# shield_confortimetro_1_1.net
KiCad netlist of a schematic drawn in EAGLE
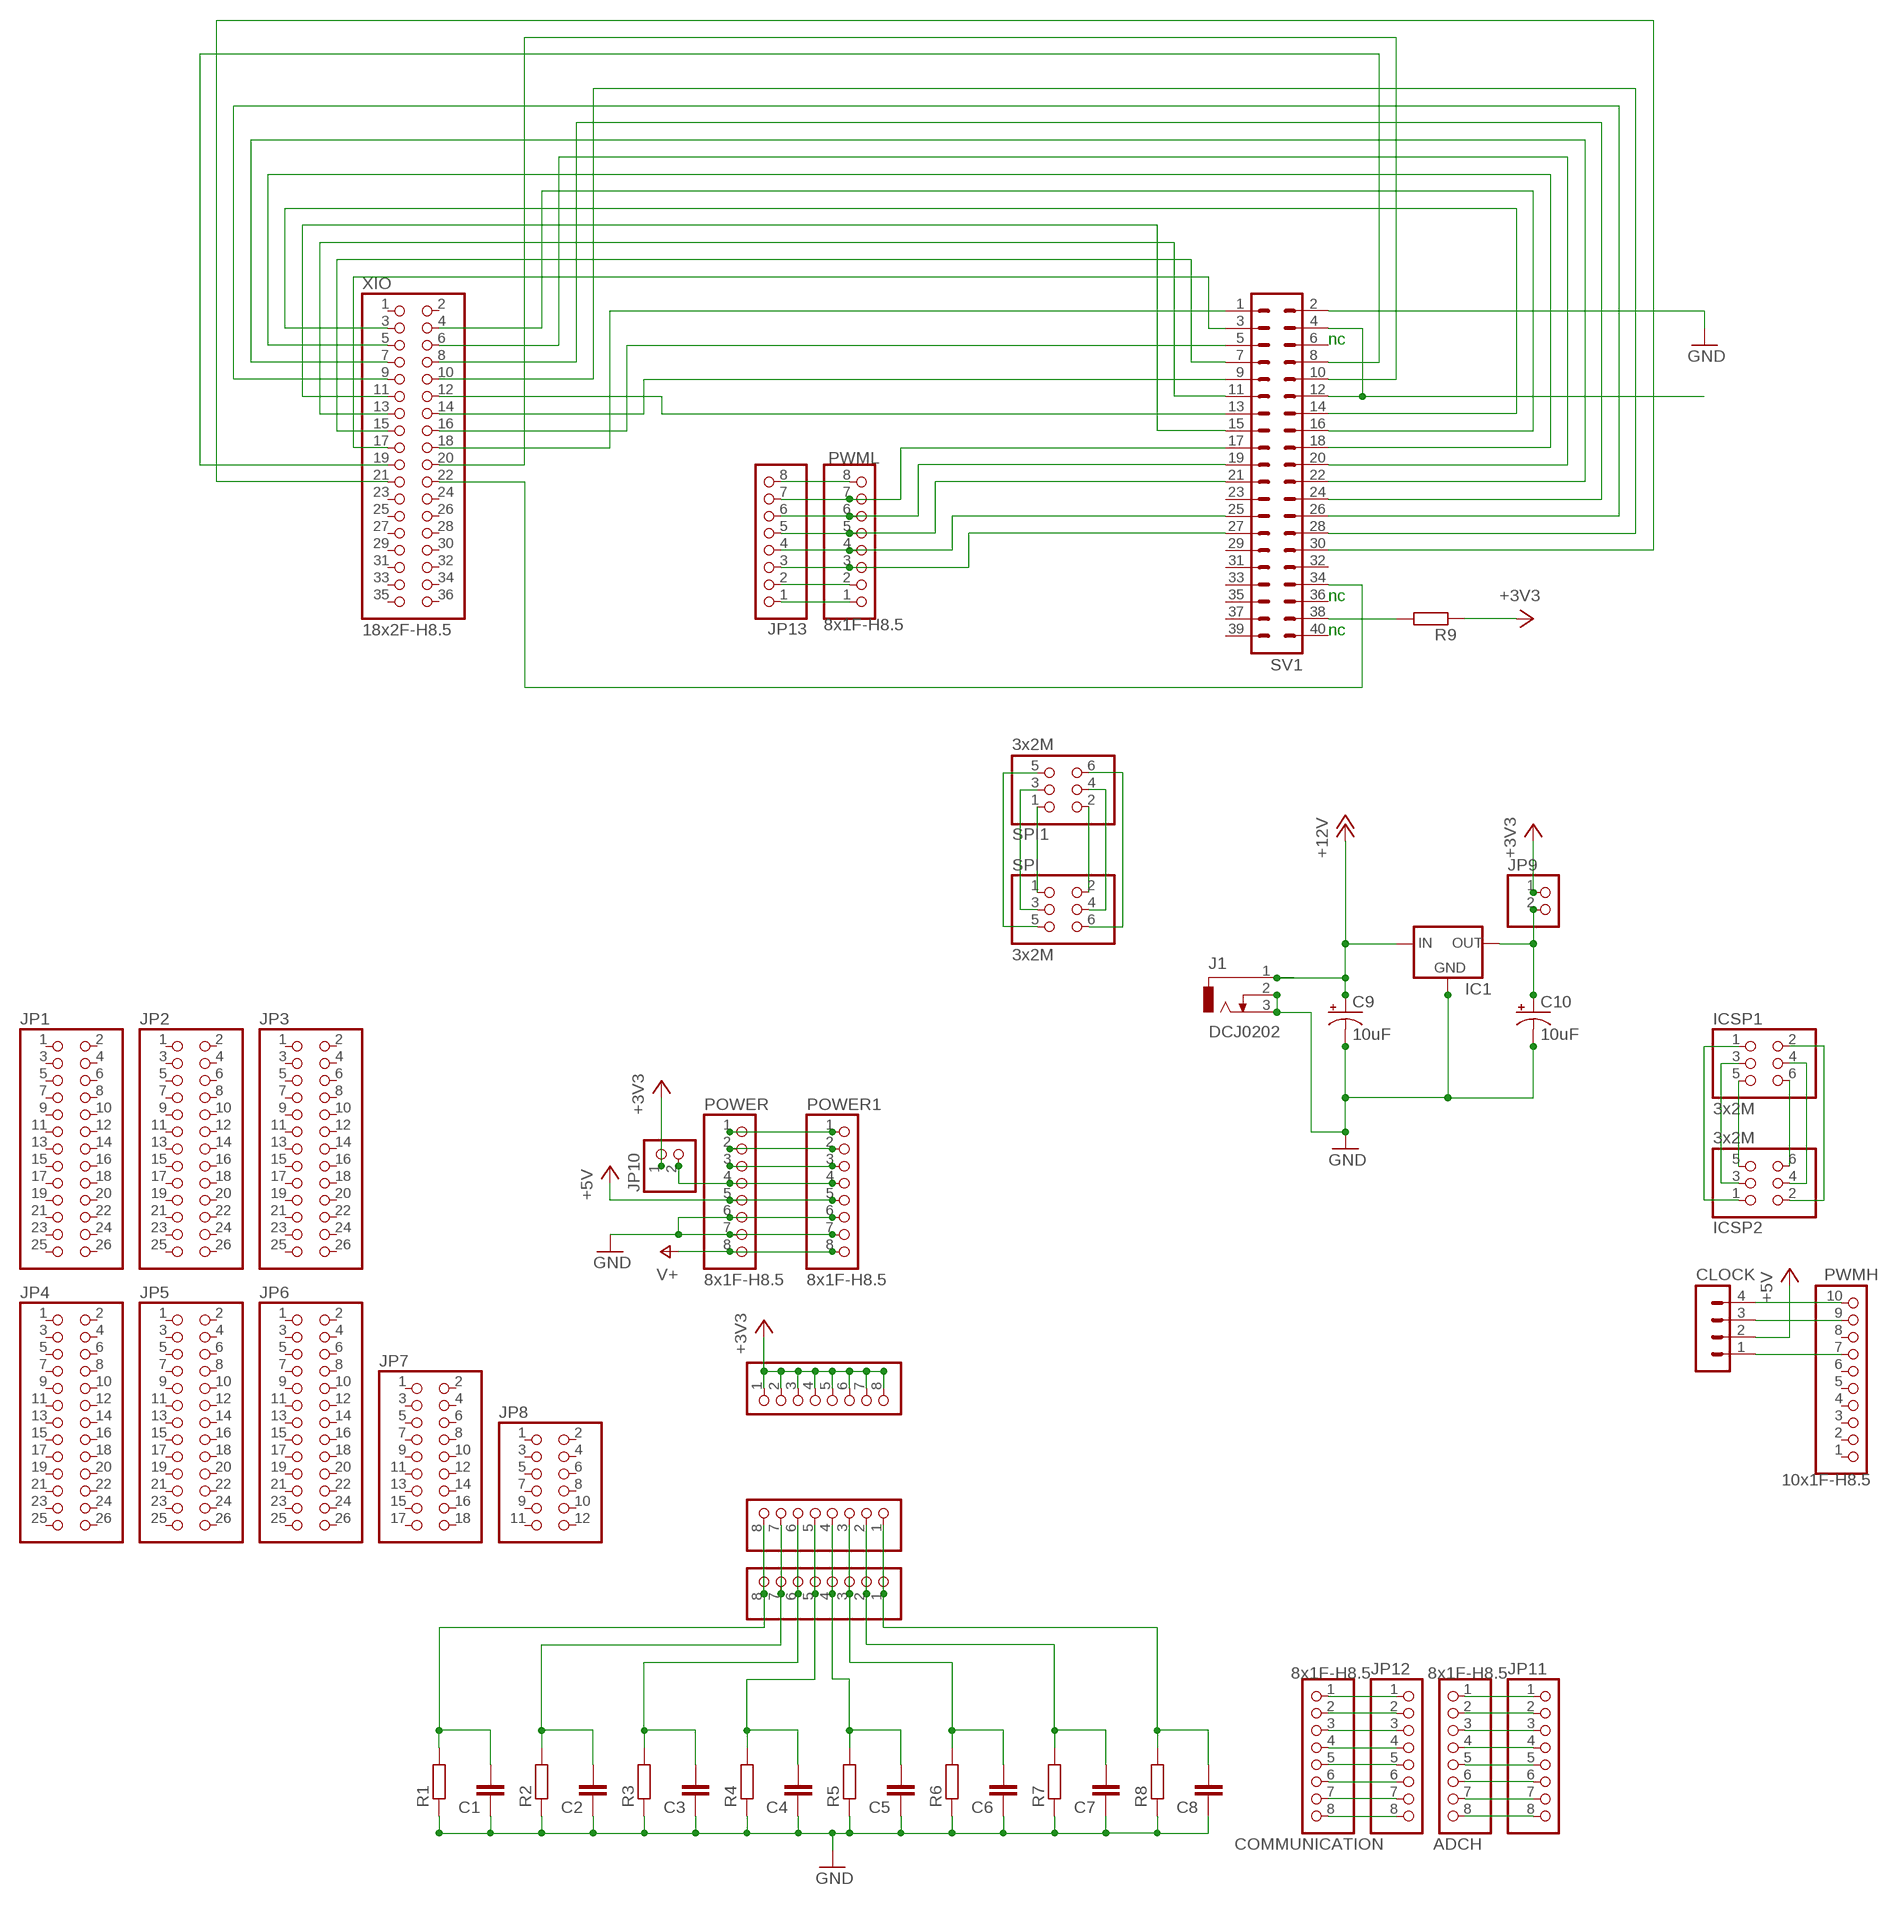
[diagram p0: schematic, sheet 1]

(export (version "E")
  (design (tool "Eeschema 10.0.6"))
  (components
    (comp (ref "ADCH")
      (value "8x1F-H8.5")
      (footprint "eagle-import:1X08")
      (libsource (lib "eagle-import") (part "PINHD-1X8"))
    )
    (comp (ref "ADCL")
      (value "8x1F-H8.5")
      (footprint "eagle-import:1X08")
      (libsource (lib "eagle-import") (part "PINHD-1X8"))
    )
    (comp (ref "C1")
      (value "C5/2.5")
      (footprint "eagle-import:C5B2.5")
      (libsource (lib "eagle-import") (part "C5/2.5"))
    )
    (comp (ref "C2")
      (value "C5/2.5")
      (footprint "eagle-import:C5B2.5")
      (libsource (lib "eagle-import") (part "C5/2.5"))
    )
    (comp (ref "C3")
      (value "C5/2.5")
      (footprint "eagle-import:C5B2.5")
      (libsource (lib "eagle-import") (part "C5/2.5"))
    )
    (comp (ref "C4")
      (value "C5/2.5")
      (footprint "eagle-import:C5B2.5")
      (libsource (lib "eagle-import") (part "C5/2.5"))
    )
    (comp (ref "C5")
      (value "C5/2.5")
      (footprint "eagle-import:C5B2.5")
      (libsource (lib "eagle-import") (part "C5/2.5"))
    )
    (comp (ref "C6")
      (value "C5/2.5")
      (footprint "eagle-import:C5B2.5")
      (libsource (lib "eagle-import") (part "C5/2.5"))
    )
    (comp (ref "C7")
      (value "C5/2.5")
      (footprint "eagle-import:C5B2.5")
      (libsource (lib "eagle-import") (part "C5/2.5"))
    )
    (comp (ref "C8")
      (value "C5/2.5")
      (footprint "eagle-import:C5B2.5")
      (libsource (lib "eagle-import") (part "C5/2.5"))
    )
    (comp (ref "C9")
      (value "10uF")
      (footprint "eagle-import:E2-5")
      (libsource (lib "eagle-import") (part "CPOL-USE2-5"))
    )
    (comp (ref "C10")
      (value "10uF")
      (footprint "eagle-import:E2-5")
      (libsource (lib "eagle-import") (part "CPOL-USE2-5"))
    )
    (comp (ref "CLOCK")
      (value "MA04-1")
      (footprint "eagle-import:MA04-1")
      (libsource (lib "eagle-import") (part "MA04-1"))
    )
    (comp (ref "COMMUNICATION")
      (value "8x1F-H8.5")
      (footprint "eagle-import:1X08")
      (libsource (lib "eagle-import") (part "PINHD-1X8"))
    )
    (comp (ref "IC1")
      (value "78XXL")
      (footprint "eagle-import:78XXL")
      (libsource (lib "eagle-import") (part "78XXL"))
    )
    (comp (ref "ICSP1")
      (value "3x2M")
      (footprint "eagle-import:2X03")
      (libsource (lib "eagle-import") (part "PINHD-2X3"))
    )
    (comp (ref "ICSP2")
      (value "3x2M")
      (footprint "eagle-import:2X03")
      (libsource (lib "eagle-import") (part "PINHD-2X3"))
    )
    (comp (ref "J1")
      (value "DCJ0202")
      (footprint "eagle-import:DCJ0202")
      (libsource (lib "eagle-import") (part "DCJ0202"))
    )
    (comp (ref "JP1")
      (value "PINHD-2X13")
      (footprint "eagle-import:2X13")
      (libsource (lib "eagle-import") (part "PINHD-2X13"))
    )
    (comp (ref "JP2")
      (value "PINHD-2X13")
      (footprint "eagle-import:2X13")
      (libsource (lib "eagle-import") (part "PINHD-2X13"))
    )
    (comp (ref "JP3")
      (value "PINHD-2X13")
      (footprint "eagle-import:2X13")
      (libsource (lib "eagle-import") (part "PINHD-2X13"))
    )
    (comp (ref "JP4")
      (value "PINHD-2X13")
      (footprint "eagle-import:2X13")
      (libsource (lib "eagle-import") (part "PINHD-2X13"))
    )
    (comp (ref "JP5")
      (value "PINHD-2X13")
      (footprint "eagle-import:2X13")
      (libsource (lib "eagle-import") (part "PINHD-2X13"))
    )
    (comp (ref "JP6")
      (value "PINHD-2X13")
      (footprint "eagle-import:2X13")
      (libsource (lib "eagle-import") (part "PINHD-2X13"))
    )
    (comp (ref "JP7")
      (value "PINHD-2X9")
      (footprint "eagle-import:2X09")
      (libsource (lib "eagle-import") (part "PINHD-2X9"))
    )
    (comp (ref "JP8")
      (value "PINHD-2X6")
      (footprint "eagle-import:2X06")
      (libsource (lib "eagle-import") (part "PINHD-2X6"))
    )
    (comp (ref "JP9")
      (value "PINHD-1X2")
      (footprint "eagle-import:1X02")
      (libsource (lib "eagle-import") (part "PINHD-1X2"))
    )
    (comp (ref "JP10")
      (value "PINHD-1X2")
      (footprint "eagle-import:1X02")
      (libsource (lib "eagle-import") (part "PINHD-1X2"))
    )
    (comp (ref "JP11")
      (value "PINHD-1X8")
      (footprint "eagle-import:1X08")
      (libsource (lib "eagle-import") (part "pinhead_PINHD-1X8"))
    )
    (comp (ref "JP12")
      (value "PINHD-1X8")
      (footprint "eagle-import:1X08")
      (libsource (lib "eagle-import") (part "pinhead_PINHD-1X8"))
    )
    (comp (ref "JP13")
      (value "PINHD-1X8")
      (footprint "eagle-import:1X08")
      (libsource (lib "eagle-import") (part "pinhead_PINHD-1X8"))
    )
    (comp (ref "POWER")
      (value "8x1F-H8.5")
      (footprint "eagle-import:1X08")
      (libsource (lib "eagle-import") (part "PINHD-1X8"))
    )
    (comp (ref "POWER1")
      (value "8x1F-H8.5")
      (footprint "eagle-import:1X08")
      (libsource (lib "eagle-import") (part "PINHD-1X8"))
    )
    (comp (ref "PWMH")
      (value "10x1F-H8.5")
      (footprint "eagle-import:1X10")
      (libsource (lib "eagle-import") (part "PINHD-1X10"))
    )
    (comp (ref "PWML")
      (value "8x1F-H8.5")
      (footprint "eagle-import:1X08")
      (libsource (lib "eagle-import") (part "PINHD-1X8"))
    )
    (comp (ref "PWML1")
      (value "8x1F-H8.5")
      (footprint "eagle-import:1X08")
      (libsource (lib "eagle-import") (part "PINHD-1X8"))
    )
    (comp (ref "PWML2")
      (value "8x1F-H8.5")
      (footprint "eagle-import:1X08")
      (libsource (lib "eagle-import") (part "PINHD-1X8"))
    )
    (comp (ref "R1")
      (value "R-EU_0204/7")
      (footprint "eagle-import:0204_7")
      (libsource (lib "eagle-import") (part "R-EU_0204/7"))
    )
    (comp (ref "R2")
      (value "R-EU_0204/7")
      (footprint "eagle-import:0204_7")
      (libsource (lib "eagle-import") (part "R-EU_0204/7"))
    )
    (comp (ref "R3")
      (value "R-EU_0204/7")
      (footprint "eagle-import:0204_7")
      (libsource (lib "eagle-import") (part "R-EU_0204/7"))
    )
    (comp (ref "R4")
      (value "R-EU_0204/7")
      (footprint "eagle-import:0204_7")
      (libsource (lib "eagle-import") (part "R-EU_0204/7"))
    )
    (comp (ref "R5")
      (value "R-EU_0204/7")
      (footprint "eagle-import:0204_7")
      (libsource (lib "eagle-import") (part "R-EU_0204/7"))
    )
    (comp (ref "R6")
      (value "R-EU_0204/7")
      (footprint "eagle-import:0204_7")
      (libsource (lib "eagle-import") (part "R-EU_0204/7"))
    )
    (comp (ref "R7")
      (value "R-EU_0204/7")
      (footprint "eagle-import:0204_7")
      (libsource (lib "eagle-import") (part "R-EU_0204/7"))
    )
    (comp (ref "R8")
      (value "R-EU_0204/7")
      (footprint "eagle-import:0204_7")
      (libsource (lib "eagle-import") (part "R-EU_0204/7"))
    )
    (comp (ref "R9")
      (value "R-EU_0204/7")
      (footprint "eagle-import:0204_7")
      (libsource (lib "eagle-import") (part "R-EU_0204/7"))
    )
    (comp (ref "SPI")
      (value "3x2M")
      (footprint "eagle-import:2X03")
      (libsource (lib "eagle-import") (part "PINHD-2X3"))
    )
    (comp (ref "SPI1")
      (value "3x2M")
      (footprint "eagle-import:2X03")
      (libsource (lib "eagle-import") (part "PINHD-2X3"))
    )
    (comp (ref "SV1")
      (value "ML40")
      (footprint "eagle-import:ML40")
      (libsource (lib "eagle-import") (part "ML40"))
    )
    (comp (ref "XIO")
      (value "18x2F-H8.5")
      (footprint "eagle-import:2X18")
      (libsource (lib "eagle-import") (part "PINHD-2X18"))
    )
  )
  (nets
    (net (code "1") (name "+3V3") (class "Default")
      (node (ref "JP10") (pin "1") (pinfunction "1_1") (pintype "passive"))
      (node (ref "JP9") (pin "1") (pinfunction "1_1") (pintype "passive"))
      (node (ref "PWML2") (pin "1") (pinfunction "1_1") (pintype "passive"))
      (node (ref "PWML2") (pin "2") (pinfunction "2_2") (pintype "passive"))
      (node (ref "PWML2") (pin "3") (pinfunction "3_3") (pintype "passive"))
      (node (ref "PWML2") (pin "4") (pinfunction "4_4") (pintype "passive"))
      (node (ref "PWML2") (pin "5") (pinfunction "5_5") (pintype "passive"))
      (node (ref "PWML2") (pin "6") (pinfunction "6_6") (pintype "passive"))
      (node (ref "PWML2") (pin "7") (pinfunction "7_7") (pintype "passive"))
      (node (ref "PWML2") (pin "8") (pinfunction "8_8") (pintype "passive"))
      (node (ref "R9") (pin "1") (pinfunction "1_1") (pintype "passive"))
    )
    (net (code "2") (name "+5V") (class "Default")
      (node (ref "CLOCK") (pin "2") (pinfunction "2_2") (pintype "passive"))
      (node (ref "POWER") (pin "5") (pinfunction "5_5") (pintype "passive"))
      (node (ref "POWER1") (pin "5") (pinfunction "5_5") (pintype "passive"))
    )
    (net (code "3") (name "+12V") (class "Default")
      (node (ref "C9") (pin "+") (pinfunction "+_+") (pintype "passive"))
      (node (ref "IC1") (pin "IN") (pinfunction "IN_IN") (pintype "input"))
      (node (ref "J1") (pin "1") (pinfunction "1_1") (pintype "passive"))
    )
    (net (code "4") (name "GND") (class "Default")
      (node (ref "C1") (pin "1") (pinfunction "1_1") (pintype "passive"))
      (node (ref "C10") (pin "-") (pinfunction "-_-") (pintype "passive"))
      (node (ref "C2") (pin "1") (pinfunction "1_1") (pintype "passive"))
      (node (ref "C3") (pin "1") (pinfunction "1_1") (pintype "passive"))
      (node (ref "C4") (pin "1") (pinfunction "1_1") (pintype "passive"))
      (node (ref "C5") (pin "1") (pinfunction "1_1") (pintype "passive"))
      (node (ref "C6") (pin "1") (pinfunction "1_1") (pintype "passive"))
      (node (ref "C7") (pin "1") (pinfunction "1_1") (pintype "passive"))
      (node (ref "C8") (pin "1") (pinfunction "1_1") (pintype "passive"))
      (node (ref "C9") (pin "-") (pinfunction "-_-") (pintype "passive"))
      (node (ref "IC1") (pin "GND") (pinfunction "GND_GND") (pintype "input"))
      (node (ref "J1") (pin "2") (pinfunction "2_2") (pintype "passive"))
      (node (ref "J1") (pin "3") (pinfunction "3_3") (pintype "passive"))
      (node (ref "POWER") (pin "6") (pinfunction "6_6") (pintype "passive"))
      (node (ref "POWER") (pin "7") (pinfunction "7_7") (pintype "passive"))
      (node (ref "POWER1") (pin "6") (pinfunction "6_6") (pintype "passive"))
      (node (ref "POWER1") (pin "7") (pinfunction "7_7") (pintype "passive"))
      (node (ref "R1") (pin "1") (pinfunction "1_1") (pintype "passive"))
      (node (ref "R2") (pin "1") (pinfunction "1_1") (pintype "passive"))
      (node (ref "R3") (pin "1") (pinfunction "1_1") (pintype "passive"))
      (node (ref "R4") (pin "1") (pinfunction "1_1") (pintype "passive"))
      (node (ref "R5") (pin "1") (pinfunction "1_1") (pintype "passive"))
      (node (ref "R6") (pin "1") (pinfunction "1_1") (pintype "passive"))
      (node (ref "R7") (pin "1") (pinfunction "1_1") (pintype "passive"))
      (node (ref "R8") (pin "1") (pinfunction "1_1") (pintype "passive"))
      (node (ref "SV1") (pin "2") (pinfunction "2_2") (pintype "passive"))
    )
    (net (code "5") (name "Net-(ADCH-Pad1)") (class "Default")
      (node (ref "ADCH") (pin "1") (pinfunction "1_1") (pintype "passive"))
      (node (ref "JP11") (pin "1") (pinfunction "1_1") (pintype "passive"))
    )
    (net (code "6") (name "Net-(ADCH-Pad2)") (class "Default")
      (node (ref "ADCH") (pin "2") (pinfunction "2_2") (pintype "passive"))
      (node (ref "JP11") (pin "2") (pinfunction "2_2") (pintype "passive"))
    )
    (net (code "7") (name "Net-(ADCH-Pad3)") (class "Default")
      (node (ref "ADCH") (pin "3") (pinfunction "3_3") (pintype "passive"))
      (node (ref "JP11") (pin "3") (pinfunction "3_3") (pintype "passive"))
    )
    (net (code "8") (name "Net-(ADCH-Pad4)") (class "Default")
      (node (ref "ADCH") (pin "4") (pinfunction "4_4") (pintype "passive"))
      (node (ref "JP11") (pin "4") (pinfunction "4_4") (pintype "passive"))
    )
    (net (code "9") (name "Net-(ADCH-Pad5)") (class "Default")
      (node (ref "ADCH") (pin "5") (pinfunction "5_5") (pintype "passive"))
      (node (ref "JP11") (pin "5") (pinfunction "5_5") (pintype "passive"))
    )
    (net (code "10") (name "Net-(ADCH-Pad6)") (class "Default")
      (node (ref "ADCH") (pin "6") (pinfunction "6_6") (pintype "passive"))
      (node (ref "JP11") (pin "6") (pinfunction "6_6") (pintype "passive"))
    )
    (net (code "11") (name "Net-(ADCH-Pad7)") (class "Default")
      (node (ref "ADCH") (pin "7") (pinfunction "7_7") (pintype "passive"))
      (node (ref "JP11") (pin "7") (pinfunction "7_7") (pintype "passive"))
    )
    (net (code "12") (name "Net-(ADCH-Pad8)") (class "Default")
      (node (ref "ADCH") (pin "8") (pinfunction "8_8") (pintype "passive"))
      (node (ref "JP11") (pin "8") (pinfunction "8_8") (pintype "passive"))
    )
    (net (code "13") (name "Net-(ADCL-Pad1)") (class "Default")
      (node (ref "ADCL") (pin "1") (pinfunction "1_1") (pintype "passive"))
      (node (ref "C8") (pin "2") (pinfunction "2_2") (pintype "passive"))
      (node (ref "PWML1") (pin "1") (pinfunction "1_1") (pintype "passive"))
      (node (ref "R8") (pin "2") (pinfunction "2_2") (pintype "passive"))
    )
    (net (code "14") (name "Net-(ADCL-Pad2)") (class "Default")
      (node (ref "ADCL") (pin "2") (pinfunction "2_2") (pintype "passive"))
      (node (ref "C7") (pin "2") (pinfunction "2_2") (pintype "passive"))
      (node (ref "PWML1") (pin "2") (pinfunction "2_2") (pintype "passive"))
      (node (ref "R7") (pin "2") (pinfunction "2_2") (pintype "passive"))
    )
    (net (code "15") (name "Net-(ADCL-Pad3)") (class "Default")
      (node (ref "ADCL") (pin "3") (pinfunction "3_3") (pintype "passive"))
      (node (ref "C6") (pin "2") (pinfunction "2_2") (pintype "passive"))
      (node (ref "PWML1") (pin "3") (pinfunction "3_3") (pintype "passive"))
      (node (ref "R6") (pin "2") (pinfunction "2_2") (pintype "passive"))
    )
    (net (code "16") (name "Net-(ADCL-Pad4)") (class "Default")
      (node (ref "ADCL") (pin "4") (pinfunction "4_4") (pintype "passive"))
      (node (ref "C5") (pin "2") (pinfunction "2_2") (pintype "passive"))
      (node (ref "PWML1") (pin "4") (pinfunction "4_4") (pintype "passive"))
      (node (ref "R5") (pin "2") (pinfunction "2_2") (pintype "passive"))
    )
    (net (code "17") (name "Net-(ADCL-Pad5)") (class "Default")
      (node (ref "ADCL") (pin "5") (pinfunction "5_5") (pintype "passive"))
      (node (ref "C4") (pin "2") (pinfunction "2_2") (pintype "passive"))
      (node (ref "PWML1") (pin "5") (pinfunction "5_5") (pintype "passive"))
      (node (ref "R4") (pin "2") (pinfunction "2_2") (pintype "passive"))
    )
    (net (code "18") (name "Net-(ADCL-Pad6)") (class "Default")
      (node (ref "ADCL") (pin "6") (pinfunction "6_6") (pintype "passive"))
      (node (ref "C3") (pin "2") (pinfunction "2_2") (pintype "passive"))
      (node (ref "PWML1") (pin "6") (pinfunction "6_6") (pintype "passive"))
      (node (ref "R3") (pin "2") (pinfunction "2_2") (pintype "passive"))
    )
    (net (code "19") (name "Net-(ADCL-Pad7)") (class "Default")
      (node (ref "ADCL") (pin "7") (pinfunction "7_7") (pintype "passive"))
      (node (ref "C2") (pin "2") (pinfunction "2_2") (pintype "passive"))
      (node (ref "PWML1") (pin "7") (pinfunction "7_7") (pintype "passive"))
      (node (ref "R2") (pin "2") (pinfunction "2_2") (pintype "passive"))
    )
    (net (code "20") (name "Net-(ADCL-Pad8)") (class "Default")
      (node (ref "ADCL") (pin "8") (pinfunction "8_8") (pintype "passive"))
      (node (ref "C1") (pin "2") (pinfunction "2_2") (pintype "passive"))
      (node (ref "PWML1") (pin "8") (pinfunction "8_8") (pintype "passive"))
      (node (ref "R1") (pin "2") (pinfunction "2_2") (pintype "passive"))
    )
    (net (code "21") (name "Net-(C10-Pad+)") (class "Default")
      (node (ref "C10") (pin "+") (pinfunction "+_+") (pintype "passive"))
      (node (ref "IC1") (pin "OUT") (pinfunction "OUT_OUT") (pintype "passive"))
      (node (ref "JP9") (pin "2") (pinfunction "2_2") (pintype "passive"))
    )
    (net (code "22") (name "Net-(CLOCK-Pad1)") (class "Default")
      (node (ref "CLOCK") (pin "1") (pinfunction "1_1") (pintype "passive"))
      (node (ref "PWMH") (pin "7") (pinfunction "7_7") (pintype "passive"))
    )
    (net (code "23") (name "Net-(CLOCK-Pad3)") (class "Default")
      (node (ref "CLOCK") (pin "3") (pinfunction "3_3") (pintype "passive"))
      (node (ref "PWMH") (pin "9") (pinfunction "9_9") (pintype "passive"))
    )
    (net (code "24") (name "Net-(CLOCK-Pad4)") (class "Default")
      (node (ref "CLOCK") (pin "4") (pinfunction "4_4") (pintype "passive"))
      (node (ref "PWMH") (pin "10") (pinfunction "10_10") (pintype "passive"))
    )
    (net (code "25") (name "Net-(COMMUNICATION-Pad1)") (class "Default")
      (node (ref "COMMUNICATION") (pin "1") (pinfunction "1_1") (pintype "passive"))
      (node (ref "JP12") (pin "1") (pinfunction "1_1") (pintype "passive"))
    )
    (net (code "26") (name "Net-(COMMUNICATION-Pad2)") (class "Default")
      (node (ref "COMMUNICATION") (pin "2") (pinfunction "2_2") (pintype "passive"))
      (node (ref "JP12") (pin "2") (pinfunction "2_2") (pintype "passive"))
    )
    (net (code "27") (name "Net-(COMMUNICATION-Pad3)") (class "Default")
      (node (ref "COMMUNICATION") (pin "3") (pinfunction "3_3") (pintype "passive"))
      (node (ref "JP12") (pin "3") (pinfunction "3_3") (pintype "passive"))
    )
    (net (code "28") (name "Net-(COMMUNICATION-Pad4)") (class "Default")
      (node (ref "COMMUNICATION") (pin "4") (pinfunction "4_4") (pintype "passive"))
      (node (ref "JP12") (pin "4") (pinfunction "4_4") (pintype "passive"))
    )
    (net (code "29") (name "Net-(COMMUNICATION-Pad5)") (class "Default")
      (node (ref "COMMUNICATION") (pin "5") (pinfunction "5_5") (pintype "passive"))
      (node (ref "JP12") (pin "5") (pinfunction "5_5") (pintype "passive"))
    )
    (net (code "30") (name "Net-(COMMUNICATION-Pad6)") (class "Default")
      (node (ref "COMMUNICATION") (pin "6") (pinfunction "6_6") (pintype "passive"))
      (node (ref "JP12") (pin "6") (pinfunction "6_6") (pintype "passive"))
    )
    (net (code "31") (name "Net-(COMMUNICATION-Pad7)") (class "Default")
      (node (ref "COMMUNICATION") (pin "7") (pinfunction "7_7") (pintype "passive"))
      (node (ref "JP12") (pin "7") (pinfunction "7_7") (pintype "passive"))
    )
    (net (code "32") (name "Net-(COMMUNICATION-Pad8)") (class "Default")
      (node (ref "COMMUNICATION") (pin "8") (pinfunction "8_8") (pintype "passive"))
      (node (ref "JP12") (pin "8") (pinfunction "8_8") (pintype "passive"))
    )
    (net (code "33") (name "Net-(ICSP1-Pad1)") (class "Default")
      (node (ref "ICSP1") (pin "1") (pinfunction "1_1") (pintype "passive"))
      (node (ref "ICSP2") (pin "1") (pinfunction "1_1") (pintype "passive"))
    )
    (net (code "34") (name "Net-(ICSP1-Pad2)") (class "Default")
      (node (ref "ICSP1") (pin "2") (pinfunction "2_2") (pintype "passive"))
      (node (ref "ICSP2") (pin "2") (pinfunction "2_2") (pintype "passive"))
    )
    (net (code "35") (name "Net-(ICSP1-Pad3)") (class "Default")
      (node (ref "ICSP1") (pin "3") (pinfunction "3_3") (pintype "passive"))
      (node (ref "ICSP2") (pin "3") (pinfunction "3_3") (pintype "passive"))
    )
    (net (code "36") (name "Net-(ICSP1-Pad4)") (class "Default")
      (node (ref "ICSP1") (pin "4") (pinfunction "4_4") (pintype "passive"))
      (node (ref "ICSP2") (pin "4") (pinfunction "4_4") (pintype "passive"))
    )
    (net (code "37") (name "Net-(ICSP1-Pad5)") (class "Default")
      (node (ref "ICSP1") (pin "5") (pinfunction "5_5") (pintype "passive"))
      (node (ref "ICSP2") (pin "5") (pinfunction "5_5") (pintype "passive"))
    )
    (net (code "38") (name "Net-(ICSP1-Pad6)") (class "Default")
      (node (ref "ICSP1") (pin "6") (pinfunction "6_6") (pintype "passive"))
      (node (ref "ICSP2") (pin "6") (pinfunction "6_6") (pintype "passive"))
    )
    (net (code "39") (name "Net-(JP10-Pad2)") (class "Default")
      (node (ref "JP10") (pin "2") (pinfunction "2_2") (pintype "passive"))
      (node (ref "POWER") (pin "4") (pinfunction "4_4") (pintype "passive"))
      (node (ref "POWER1") (pin "4") (pinfunction "4_4") (pintype "passive"))
    )
    (net (code "40") (name "Net-(JP13-Pad1)") (class "Default")
      (node (ref "JP13") (pin "1") (pinfunction "1_1") (pintype "passive"))
      (node (ref "PWML") (pin "1") (pinfunction "1_1") (pintype "passive"))
    )
    (net (code "41") (name "Net-(JP13-Pad2)") (class "Default")
      (node (ref "JP13") (pin "2") (pinfunction "2_2") (pintype "passive"))
      (node (ref "PWML") (pin "2") (pinfunction "2_2") (pintype "passive"))
    )
    (net (code "42") (name "Net-(JP13-Pad3)") (class "Default")
      (node (ref "JP13") (pin "3") (pinfunction "3_3") (pintype "passive"))
      (node (ref "PWML") (pin "3") (pinfunction "3_3") (pintype "passive"))
      (node (ref "SV1") (pin "27") (pinfunction "27_27") (pintype "passive"))
    )
    (net (code "43") (name "Net-(JP13-Pad4)") (class "Default")
      (node (ref "JP13") (pin "4") (pinfunction "4_4") (pintype "passive"))
      (node (ref "PWML") (pin "4") (pinfunction "4_4") (pintype "passive"))
      (node (ref "SV1") (pin "25") (pinfunction "25_25") (pintype "passive"))
    )
    (net (code "44") (name "Net-(JP13-Pad5)") (class "Default")
      (node (ref "JP13") (pin "5") (pinfunction "5_5") (pintype "passive"))
      (node (ref "PWML") (pin "5") (pinfunction "5_5") (pintype "passive"))
      (node (ref "SV1") (pin "21") (pinfunction "21_21") (pintype "passive"))
    )
    (net (code "45") (name "Net-(JP13-Pad6)") (class "Default")
      (node (ref "JP13") (pin "6") (pinfunction "6_6") (pintype "passive"))
      (node (ref "PWML") (pin "6") (pinfunction "6_6") (pintype "passive"))
      (node (ref "SV1") (pin "19") (pinfunction "19_19") (pintype "passive"))
    )
    (net (code "46") (name "Net-(JP13-Pad7)") (class "Default")
      (node (ref "JP13") (pin "7") (pinfunction "7_7") (pintype "passive"))
      (node (ref "PWML") (pin "7") (pinfunction "7_7") (pintype "passive"))
      (node (ref "SV1") (pin "17") (pinfunction "17_17") (pintype "passive"))
    )
    (net (code "47") (name "Net-(JP13-Pad8)") (class "Default")
      (node (ref "JP13") (pin "8") (pinfunction "8_8") (pintype "passive"))
      (node (ref "PWML") (pin "8") (pinfunction "8_8") (pintype "passive"))
    )
    (net (code "48") (name "Net-(POWER-Pad1)") (class "Default")
      (node (ref "POWER") (pin "1") (pinfunction "1_1") (pintype "passive"))
      (node (ref "POWER1") (pin "1") (pinfunction "1_1") (pintype "passive"))
    )
    (net (code "49") (name "Net-(POWER-Pad2)") (class "Default")
      (node (ref "POWER") (pin "2") (pinfunction "2_2") (pintype "passive"))
      (node (ref "POWER1") (pin "2") (pinfunction "2_2") (pintype "passive"))
    )
    (net (code "50") (name "Net-(POWER-Pad3)") (class "Default")
      (node (ref "POWER") (pin "3") (pinfunction "3_3") (pintype "passive"))
      (node (ref "POWER1") (pin "3") (pinfunction "3_3") (pintype "passive"))
    )
    (net (code "51") (name "Net-(R9-Pad2)") (class "Default")
      (node (ref "R9") (pin "2") (pinfunction "2_2") (pintype "passive"))
      (node (ref "SV1") (pin "38") (pinfunction "38_38") (pintype "passive"))
    )
    (net (code "52") (name "Net-(SPI-Pad1)") (class "Default")
      (node (ref "SPI") (pin "1") (pinfunction "1_1") (pintype "passive"))
      (node (ref "SPI1") (pin "1") (pinfunction "1_1") (pintype "passive"))
    )
    (net (code "53") (name "Net-(SPI-Pad2)") (class "Default")
      (node (ref "SPI") (pin "2") (pinfunction "2_2") (pintype "passive"))
      (node (ref "SPI1") (pin "2") (pinfunction "2_2") (pintype "passive"))
    )
    (net (code "54") (name "Net-(SPI-Pad3)") (class "Default")
      (node (ref "SPI") (pin "3") (pinfunction "3_3") (pintype "passive"))
      (node (ref "SPI1") (pin "3") (pinfunction "3_3") (pintype "passive"))
    )
    (net (code "55") (name "Net-(SPI-Pad4)") (class "Default")
      (node (ref "SPI") (pin "4") (pinfunction "4_4") (pintype "passive"))
      (node (ref "SPI1") (pin "4") (pinfunction "4_4") (pintype "passive"))
    )
    (net (code "56") (name "Net-(SPI-Pad5)") (class "Default")
      (node (ref "SPI") (pin "5") (pinfunction "5_5") (pintype "passive"))
      (node (ref "SPI1") (pin "5") (pinfunction "5_5") (pintype "passive"))
    )
    (net (code "57") (name "Net-(SPI-Pad6)") (class "Default")
      (node (ref "SPI") (pin "6") (pinfunction "6_6") (pintype "passive"))
      (node (ref "SPI1") (pin "6") (pinfunction "6_6") (pintype "passive"))
    )
    (net (code "58") (name "Net-(SV1-Pad1)") (class "Default")
      (node (ref "SV1") (pin "1") (pinfunction "1_1") (pintype "passive"))
      (node (ref "XIO") (pin "18") (pinfunction "18_18") (pintype "passive"))
    )
    (net (code "59") (name "Net-(SV1-Pad3)") (class "Default")
      (node (ref "SV1") (pin "3") (pinfunction "3_3") (pintype "passive"))
      (node (ref "XIO") (pin "17") (pinfunction "17_17") (pintype "passive"))
    )
    (net (code "60") (name "Net-(SV1-Pad5)") (class "Default")
      (node (ref "SV1") (pin "5") (pinfunction "5_5") (pintype "passive"))
      (node (ref "XIO") (pin "16") (pinfunction "16_16") (pintype "passive"))
    )
    (net (code "61") (name "Net-(SV1-Pad7)") (class "Default")
      (node (ref "SV1") (pin "7") (pinfunction "7_7") (pintype "passive"))
      (node (ref "XIO") (pin "15") (pinfunction "15_15") (pintype "passive"))
    )
    (net (code "62") (name "Net-(SV1-Pad8)") (class "Default")
      (node (ref "SV1") (pin "8") (pinfunction "8_8") (pintype "passive"))
      (node (ref "XIO") (pin "19") (pinfunction "19_19") (pintype "passive"))
    )
    (net (code "63") (name "Net-(SV1-Pad9)") (class "Default")
      (node (ref "SV1") (pin "9") (pinfunction "9_9") (pintype "passive"))
      (node (ref "XIO") (pin "14") (pinfunction "14_14") (pintype "passive"))
    )
    (net (code "64") (name "Net-(SV1-Pad10)") (class "Default")
      (node (ref "SV1") (pin "10") (pinfunction "10_10") (pintype "passive"))
      (node (ref "XIO") (pin "20") (pinfunction "20_20") (pintype "passive"))
    )
    (net (code "65") (name "Net-(SV1-Pad11)") (class "Default")
      (node (ref "SV1") (pin "11") (pinfunction "11_11") (pintype "passive"))
      (node (ref "XIO") (pin "13") (pinfunction "13_13") (pintype "passive"))
    )
    (net (code "66") (name "Net-(SV1-Pad12)") (class "Default")
      (node (ref "SV1") (pin "12") (pinfunction "12_12") (pintype "passive"))
      (node (ref "SV1") (pin "4") (pinfunction "4_4") (pintype "passive"))
    )
    (net (code "67") (name "Net-(SV1-Pad13)") (class "Default")
      (node (ref "SV1") (pin "13") (pinfunction "13_13") (pintype "passive"))
      (node (ref "XIO") (pin "12") (pinfunction "12_12") (pintype "passive"))
    )
    (net (code "68") (name "Net-(SV1-Pad14)") (class "Default")
      (node (ref "SV1") (pin "14") (pinfunction "14_14") (pintype "passive"))
      (node (ref "XIO") (pin "3") (pinfunction "3_3") (pintype "passive"))
    )
    (net (code "69") (name "Net-(SV1-Pad15)") (class "Default")
      (node (ref "SV1") (pin "15") (pinfunction "15_15") (pintype "passive"))
      (node (ref "XIO") (pin "11") (pinfunction "11_11") (pintype "passive"))
    )
    (net (code "70") (name "Net-(SV1-Pad16)") (class "Default")
      (node (ref "SV1") (pin "16") (pinfunction "16_16") (pintype "passive"))
      (node (ref "XIO") (pin "4") (pinfunction "4_4") (pintype "passive"))
    )
    (net (code "71") (name "Net-(SV1-Pad18)") (class "Default")
      (node (ref "SV1") (pin "18") (pinfunction "18_18") (pintype "passive"))
      (node (ref "XIO") (pin "5") (pinfunction "5_5") (pintype "passive"))
    )
    (net (code "72") (name "Net-(SV1-Pad20)") (class "Default")
      (node (ref "SV1") (pin "20") (pinfunction "20_20") (pintype "passive"))
      (node (ref "XIO") (pin "6") (pinfunction "6_6") (pintype "passive"))
    )
    (net (code "73") (name "Net-(SV1-Pad22)") (class "Default")
      (node (ref "SV1") (pin "22") (pinfunction "22_22") (pintype "passive"))
      (node (ref "XIO") (pin "7") (pinfunction "7_7") (pintype "passive"))
    )
    (net (code "74") (name "Net-(SV1-Pad24)") (class "Default")
      (node (ref "SV1") (pin "24") (pinfunction "24_24") (pintype "passive"))
      (node (ref "XIO") (pin "8") (pinfunction "8_8") (pintype "passive"))
    )
    (net (code "75") (name "Net-(SV1-Pad26)") (class "Default")
      (node (ref "SV1") (pin "26") (pinfunction "26_26") (pintype "passive"))
      (node (ref "XIO") (pin "9") (pinfunction "9_9") (pintype "passive"))
    )
    (net (code "76") (name "Net-(SV1-Pad28)") (class "Default")
      (node (ref "SV1") (pin "28") (pinfunction "28_28") (pintype "passive"))
      (node (ref "XIO") (pin "10") (pinfunction "10_10") (pintype "passive"))
    )
    (net (code "77") (name "Net-(SV1-Pad30)") (class "Default")
      (node (ref "SV1") (pin "30") (pinfunction "30_30") (pintype "passive"))
      (node (ref "XIO") (pin "21") (pinfunction "21_21") (pintype "passive"))
    )
    (net (code "78") (name "Net-(SV1-Pad34)") (class "Default")
      (node (ref "SV1") (pin "34") (pinfunction "34_34") (pintype "passive"))
      (node (ref "XIO") (pin "22") (pinfunction "22_22") (pintype "passive"))
    )
    (net (code "79") (name "V+") (class "Default")
      (node (ref "POWER") (pin "8") (pinfunction "8_8") (pintype "passive"))
      (node (ref "POWER1") (pin "8") (pinfunction "8_8") (pintype "passive"))
    )
    (net (code "80") (name "unconnected-(JP1-Pad1)") (class "Default")
      (node (ref "JP1") (pin "1") (pinfunction "1_1") (pintype "passive"))
    )
    (net (code "81") (name "unconnected-(JP1-Pad2)") (class "Default")
      (node (ref "JP1") (pin "2") (pinfunction "2_2") (pintype "passive"))
    )
    (net (code "82") (name "unconnected-(JP1-Pad3)") (class "Default")
      (node (ref "JP1") (pin "3") (pinfunction "3_3") (pintype "passive"))
    )
    (net (code "83") (name "unconnected-(JP1-Pad4)") (class "Default")
      (node (ref "JP1") (pin "4") (pinfunction "4_4") (pintype "passive"))
    )
    (net (code "84") (name "unconnected-(JP1-Pad5)") (class "Default")
      (node (ref "JP1") (pin "5") (pinfunction "5_5") (pintype "passive"))
    )
    (net (code "85") (name "unconnected-(JP1-Pad6)") (class "Default")
      (node (ref "JP1") (pin "6") (pinfunction "6_6") (pintype "passive"))
    )
    (net (code "86") (name "unconnected-(JP1-Pad7)") (class "Default")
      (node (ref "JP1") (pin "7") (pinfunction "7_7") (pintype "passive"))
    )
    (net (code "87") (name "unconnected-(JP1-Pad8)") (class "Default")
      (node (ref "JP1") (pin "8") (pinfunction "8_8") (pintype "passive"))
    )
    (net (code "88") (name "unconnected-(JP1-Pad9)") (class "Default")
      (node (ref "JP1") (pin "9") (pinfunction "9_9") (pintype "passive"))
    )
    (net (code "89") (name "unconnected-(JP1-Pad10)") (class "Default")
      (node (ref "JP1") (pin "10") (pinfunction "10_10") (pintype "passive"))
    )
    (net (code "90") (name "unconnected-(JP1-Pad11)") (class "Default")
      (node (ref "JP1") (pin "11") (pinfunction "11_11") (pintype "passive"))
    )
    (net (code "91") (name "unconnected-(JP1-Pad12)") (class "Default")
      (node (ref "JP1") (pin "12") (pinfunction "12_12") (pintype "passive"))
    )
    (net (code "92") (name "unconnected-(JP1-Pad13)") (class "Default")
      (node (ref "JP1") (pin "13") (pinfunction "13_13") (pintype "passive"))
    )
    (net (code "93") (name "unconnected-(JP1-Pad14)") (class "Default")
      (node (ref "JP1") (pin "14") (pinfunction "14_14") (pintype "passive"))
    )
    (net (code "94") (name "unconnected-(JP1-Pad15)") (class "Default")
      (node (ref "JP1") (pin "15") (pinfunction "15_15") (pintype "passive"))
    )
    (net (code "95") (name "unconnected-(JP1-Pad16)") (class "Default")
      (node (ref "JP1") (pin "16") (pinfunction "16_16") (pintype "passive"))
    )
    (net (code "96") (name "unconnected-(JP1-Pad17)") (class "Default")
      (node (ref "JP1") (pin "17") (pinfunction "17_17") (pintype "passive"))
    )
    (net (code "97") (name "unconnected-(JP1-Pad18)") (class "Default")
      (node (ref "JP1") (pin "18") (pinfunction "18_18") (pintype "passive"))
    )
    (net (code "98") (name "unconnected-(JP1-Pad19)") (class "Default")
      (node (ref "JP1") (pin "19") (pinfunction "19_19") (pintype "passive"))
    )
    (net (code "99") (name "unconnected-(JP1-Pad20)") (class "Default")
      (node (ref "JP1") (pin "20") (pinfunction "20_20") (pintype "passive"))
    )
    (net (code "100") (name "unconnected-(JP1-Pad21)") (class "Default")
      (node (ref "JP1") (pin "21") (pinfunction "21_21") (pintype "passive"))
    )
    (net (code "101") (name "unconnected-(JP1-Pad22)") (class "Default")
      (node (ref "JP1") (pin "22") (pinfunction "22_22") (pintype "passive"))
    )
    (net (code "102") (name "unconnected-(JP1-Pad23)") (class "Default")
      (node (ref "JP1") (pin "23") (pinfunction "23_23") (pintype "passive"))
    )
    (net (code "103") (name "unconnected-(JP1-Pad24)") (class "Default")
      (node (ref "JP1") (pin "24") (pinfunction "24_24") (pintype "passive"))
    )
    (net (code "104") (name "unconnected-(JP1-Pad25)") (class "Default")
      (node (ref "JP1") (pin "25") (pinfunction "25_25") (pintype "passive"))
    )
    (net (code "105") (name "unconnected-(JP1-Pad26)") (class "Default")
      (node (ref "JP1") (pin "26") (pinfunction "26_26") (pintype "passive"))
    )
    (net (code "106") (name "unconnected-(JP2-Pad1)") (class "Default")
      (node (ref "JP2") (pin "1") (pinfunction "1_1") (pintype "passive"))
    )
    (net (code "107") (name "unconnected-(JP2-Pad2)") (class "Default")
      (node (ref "JP2") (pin "2") (pinfunction "2_2") (pintype "passive"))
    )
    (net (code "108") (name "unconnected-(JP2-Pad3)") (class "Default")
      (node (ref "JP2") (pin "3") (pinfunction "3_3") (pintype "passive"))
    )
    (net (code "109") (name "unconnected-(JP2-Pad4)") (class "Default")
      (node (ref "JP2") (pin "4") (pinfunction "4_4") (pintype "passive"))
    )
    (net (code "110") (name "unconnected-(JP2-Pad5)") (class "Default")
      (node (ref "JP2") (pin "5") (pinfunction "5_5") (pintype "passive"))
    )
    (net (code "111") (name "unconnected-(JP2-Pad6)") (class "Default")
      (node (ref "JP2") (pin "6") (pinfunction "6_6") (pintype "passive"))
    )
    (net (code "112") (name "unconnected-(JP2-Pad7)") (class "Default")
      (node (ref "JP2") (pin "7") (pinfunction "7_7") (pintype "passive"))
    )
    (net (code "113") (name "unconnected-(JP2-Pad8)") (class "Default")
      (node (ref "JP2") (pin "8") (pinfunction "8_8") (pintype "passive"))
    )
    (net (code "114") (name "unconnected-(JP2-Pad9)") (class "Default")
      (node (ref "JP2") (pin "9") (pinfunction "9_9") (pintype "passive"))
    )
    (net (code "115") (name "unconnected-(JP2-Pad10)") (class "Default")
      (node (ref "JP2") (pin "10") (pinfunction "10_10") (pintype "passive"))
    )
    (net (code "116") (name "unconnected-(JP2-Pad11)") (class "Default")
      (node (ref "JP2") (pin "11") (pinfunction "11_11") (pintype "passive"))
    )
    (net (code "117") (name "unconnected-(JP2-Pad12)") (class "Default")
      (node (ref "JP2") (pin "12") (pinfunction "12_12") (pintype "passive"))
    )
    (net (code "118") (name "unconnected-(JP2-Pad13)") (class "Default")
      (node (ref "JP2") (pin "13") (pinfunction "13_13") (pintype "passive"))
    )
    (net (code "119") (name "unconnected-(JP2-Pad14)") (class "Default")
      (node (ref "JP2") (pin "14") (pinfunction "14_14") (pintype "passive"))
    )
    (net (code "120") (name "unconnected-(JP2-Pad15)") (class "Default")
      (node (ref "JP2") (pin "15") (pinfunction "15_15") (pintype "passive"))
    )
    (net (code "121") (name "unconnected-(JP2-Pad16)") (class "Default")
      (node (ref "JP2") (pin "16") (pinfunction "16_16") (pintype "passive"))
    )
    (net (code "122") (name "unconnected-(JP2-Pad17)") (class "Default")
      (node (ref "JP2") (pin "17") (pinfunction "17_17") (pintype "passive"))
    )
    (net (code "123") (name "unconnected-(JP2-Pad18)") (class "Default")
      (node (ref "JP2") (pin "18") (pinfunction "18_18") (pintype "passive"))
    )
    (net (code "124") (name "unconnected-(JP2-Pad19)") (class "Default")
      (node (ref "JP2") (pin "19") (pinfunction "19_19") (pintype "passive"))
    )
    (net (code "125") (name "unconnected-(JP2-Pad20)") (class "Default")
      (node (ref "JP2") (pin "20") (pinfunction "20_20") (pintype "passive"))
    )
    (net (code "126") (name "unconnected-(JP2-Pad21)") (class "Default")
      (node (ref "JP2") (pin "21") (pinfunction "21_21") (pintype "passive"))
    )
    (net (code "127") (name "unconnected-(JP2-Pad22)") (class "Default")
      (node (ref "JP2") (pin "22") (pinfunction "22_22") (pintype "passive"))
    )
    (net (code "128") (name "unconnected-(JP2-Pad23)") (class "Default")
      (node (ref "JP2") (pin "23") (pinfunction "23_23") (pintype "passive"))
    )
    (net (code "129") (name "unconnected-(JP2-Pad24)") (class "Default")
      (node (ref "JP2") (pin "24") (pinfunction "24_24") (pintype "passive"))
    )
    (net (code "130") (name "unconnected-(JP2-Pad25)") (class "Default")
      (node (ref "JP2") (pin "25") (pinfunction "25_25") (pintype "passive"))
    )
    (net (code "131") (name "unconnected-(JP2-Pad26)") (class "Default")
      (node (ref "JP2") (pin "26") (pinfunction "26_26") (pintype "passive"))
    )
    (net (code "132") (name "unconnected-(JP3-Pad1)") (class "Default")
      (node (ref "JP3") (pin "1") (pinfunction "1_1") (pintype "passive"))
    )
    (net (code "133") (name "unconnected-(JP3-Pad2)") (class "Default")
      (node (ref "JP3") (pin "2") (pinfunction "2_2") (pintype "passive"))
    )
    (net (code "134") (name "unconnected-(JP3-Pad3)") (class "Default")
      (node (ref "JP3") (pin "3") (pinfunction "3_3") (pintype "passive"))
    )
    (net (code "135") (name "unconnected-(JP3-Pad4)") (class "Default")
      (node (ref "JP3") (pin "4") (pinfunction "4_4") (pintype "passive"))
    )
    (net (code "136") (name "unconnected-(JP3-Pad5)") (class "Default")
      (node (ref "JP3") (pin "5") (pinfunction "5_5") (pintype "passive"))
    )
    (net (code "137") (name "unconnected-(JP3-Pad6)") (class "Default")
      (node (ref "JP3") (pin "6") (pinfunction "6_6") (pintype "passive"))
    )
    (net (code "138") (name "unconnected-(JP3-Pad7)") (class "Default")
      (node (ref "JP3") (pin "7") (pinfunction "7_7") (pintype "passive"))
    )
    (net (code "139") (name "unconnected-(JP3-Pad8)") (class "Default")
      (node (ref "JP3") (pin "8") (pinfunction "8_8") (pintype "passive"))
    )
    (net (code "140") (name "unconnected-(JP3-Pad9)") (class "Default")
      (node (ref "JP3") (pin "9") (pinfunction "9_9") (pintype "passive"))
    )
    (net (code "141") (name "unconnected-(JP3-Pad10)") (class "Default")
      (node (ref "JP3") (pin "10") (pinfunction "10_10") (pintype "passive"))
    )
    (net (code "142") (name "unconnected-(JP3-Pad11)") (class "Default")
      (node (ref "JP3") (pin "11") (pinfunction "11_11") (pintype "passive"))
    )
    (net (code "143") (name "unconnected-(JP3-Pad12)") (class "Default")
      (node (ref "JP3") (pin "12") (pinfunction "12_12") (pintype "passive"))
    )
    (net (code "144") (name "unconnected-(JP3-Pad13)") (class "Default")
      (node (ref "JP3") (pin "13") (pinfunction "13_13") (pintype "passive"))
    )
    (net (code "145") (name "unconnected-(JP3-Pad14)") (class "Default")
      (node (ref "JP3") (pin "14") (pinfunction "14_14") (pintype "passive"))
    )
    (net (code "146") (name "unconnected-(JP3-Pad15)") (class "Default")
      (node (ref "JP3") (pin "15") (pinfunction "15_15") (pintype "passive"))
    )
    (net (code "147") (name "unconnected-(JP3-Pad16)") (class "Default")
      (node (ref "JP3") (pin "16") (pinfunction "16_16") (pintype "passive"))
    )
    (net (code "148") (name "unconnected-(JP3-Pad17)") (class "Default")
      (node (ref "JP3") (pin "17") (pinfunction "17_17") (pintype "passive"))
    )
    (net (code "149") (name "unconnected-(JP3-Pad18)") (class "Default")
      (node (ref "JP3") (pin "18") (pinfunction "18_18") (pintype "passive"))
    )
    (net (code "150") (name "unconnected-(JP3-Pad19)") (class "Default")
      (node (ref "JP3") (pin "19") (pinfunction "19_19") (pintype "passive"))
    )
    (net (code "151") (name "unconnected-(JP3-Pad20)") (class "Default")
      (node (ref "JP3") (pin "20") (pinfunction "20_20") (pintype "passive"))
    )
    (net (code "152") (name "unconnected-(JP3-Pad21)") (class "Default")
      (node (ref "JP3") (pin "21") (pinfunction "21_21") (pintype "passive"))
    )
    (net (code "153") (name "unconnected-(JP3-Pad22)") (class "Default")
      (node (ref "JP3") (pin "22") (pinfunction "22_22") (pintype "passive"))
    )
    (net (code "154") (name "unconnected-(JP3-Pad23)") (class "Default")
      (node (ref "JP3") (pin "23") (pinfunction "23_23") (pintype "passive"))
    )
    (net (code "155") (name "unconnected-(JP3-Pad24)") (class "Default")
      (node (ref "JP3") (pin "24") (pinfunction "24_24") (pintype "passive"))
    )
    (net (code "156") (name "unconnected-(JP3-Pad25)") (class "Default")
      (node (ref "JP3") (pin "25") (pinfunction "25_25") (pintype "passive"))
    )
    (net (code "157") (name "unconnected-(JP3-Pad26)") (class "Default")
      (node (ref "JP3") (pin "26") (pinfunction "26_26") (pintype "passive"))
    )
    (net (code "158") (name "unconnected-(JP4-Pad1)") (class "Default")
      (node (ref "JP4") (pin "1") (pinfunction "1_1") (pintype "passive"))
    )
    (net (code "159") (name "unconnected-(JP4-Pad2)") (class "Default")
      (node (ref "JP4") (pin "2") (pinfunction "2_2") (pintype "passive"))
    )
    (net (code "160") (name "unconnected-(JP4-Pad3)") (class "Default")
      (node (ref "JP4") (pin "3") (pinfunction "3_3") (pintype "passive"))
    )
    (net (code "161") (name "unconnected-(JP4-Pad4)") (class "Default")
      (node (ref "JP4") (pin "4") (pinfunction "4_4") (pintype "passive"))
    )
    (net (code "162") (name "unconnected-(JP4-Pad5)") (class "Default")
      (node (ref "JP4") (pin "5") (pinfunction "5_5") (pintype "passive"))
    )
    (net (code "163") (name "unconnected-(JP4-Pad6)") (class "Default")
      (node (ref "JP4") (pin "6") (pinfunction "6_6") (pintype "passive"))
    )
    (net (code "164") (name "unconnected-(JP4-Pad7)") (class "Default")
      (node (ref "JP4") (pin "7") (pinfunction "7_7") (pintype "passive"))
    )
    (net (code "165") (name "unconnected-(JP4-Pad8)") (class "Default")
      (node (ref "JP4") (pin "8") (pinfunction "8_8") (pintype "passive"))
    )
    (net (code "166") (name "unconnected-(JP4-Pad9)") (class "Default")
      (node (ref "JP4") (pin "9") (pinfunction "9_9") (pintype "passive"))
    )
    (net (code "167") (name "unconnected-(JP4-Pad10)") (class "Default")
      (node (ref "JP4") (pin "10") (pinfunction "10_10") (pintype "passive"))
    )
    (net (code "168") (name "unconnected-(JP4-Pad11)") (class "Default")
      (node (ref "JP4") (pin "11") (pinfunction "11_11") (pintype "passive"))
    )
    (net (code "169") (name "unconnected-(JP4-Pad12)") (class "Default")
      (node (ref "JP4") (pin "12") (pinfunction "12_12") (pintype "passive"))
    )
    (net (code "170") (name "unconnected-(JP4-Pad13)") (class "Default")
      (node (ref "JP4") (pin "13") (pinfunction "13_13") (pintype "passive"))
    )
    (net (code "171") (name "unconnected-(JP4-Pad14)") (class "Default")
      (node (ref "JP4") (pin "14") (pinfunction "14_14") (pintype "passive"))
    )
    (net (code "172") (name "unconnected-(JP4-Pad15)") (class "Default")
      (node (ref "JP4") (pin "15") (pinfunction "15_15") (pintype "passive"))
    )
    (net (code "173") (name "unconnected-(JP4-Pad16)") (class "Default")
      (node (ref "JP4") (pin "16") (pinfunction "16_16") (pintype "passive"))
    )
    (net (code "174") (name "unconnected-(JP4-Pad17)") (class "Default")
      (node (ref "JP4") (pin "17") (pinfunction "17_17") (pintype "passive"))
    )
    (net (code "175") (name "unconnected-(JP4-Pad18)") (class "Default")
      (node (ref "JP4") (pin "18") (pinfunction "18_18") (pintype "passive"))
    )
    (net (code "176") (name "unconnected-(JP4-Pad19)") (class "Default")
      (node (ref "JP4") (pin "19") (pinfunction "19_19") (pintype "passive"))
    )
    (net (code "177") (name "unconnected-(JP4-Pad20)") (class "Default")
      (node (ref "JP4") (pin "20") (pinfunction "20_20") (pintype "passive"))
    )
    (net (code "178") (name "unconnected-(JP4-Pad21)") (class "Default")
      (node (ref "JP4") (pin "21") (pinfunction "21_21") (pintype "passive"))
    )
    (net (code "179") (name "unconnected-(JP4-Pad22)") (class "Default")
      (node (ref "JP4") (pin "22") (pinfunction "22_22") (pintype "passive"))
    )
    (net (code "180") (name "unconnected-(JP4-Pad23)") (class "Default")
      (node (ref "JP4") (pin "23") (pinfunction "23_23") (pintype "passive"))
    )
    (net (code "181") (name "unconnected-(JP4-Pad24)") (class "Default")
      (node (ref "JP4") (pin "24") (pinfunction "24_24") (pintype "passive"))
    )
    (net (code "182") (name "unconnected-(JP4-Pad25)") (class "Default")
      (node (ref "JP4") (pin "25") (pinfunction "25_25") (pintype "passive"))
    )
    (net (code "183") (name "unconnected-(JP4-Pad26)") (class "Default")
      (node (ref "JP4") (pin "26") (pinfunction "26_26") (pintype "passive"))
    )
    (net (code "184") (name "unconnected-(JP5-Pad1)") (class "Default")
      (node (ref "JP5") (pin "1") (pinfunction "1_1") (pintype "passive"))
    )
    (net (code "185") (name "unconnected-(JP5-Pad2)") (class "Default")
      (node (ref "JP5") (pin "2") (pinfunction "2_2") (pintype "passive"))
    )
    (net (code "186") (name "unconnected-(JP5-Pad3)") (class "Default")
      (node (ref "JP5") (pin "3") (pinfunction "3_3") (pintype "passive"))
    )
    (net (code "187") (name "unconnected-(JP5-Pad4)") (class "Default")
      (node (ref "JP5") (pin "4") (pinfunction "4_4") (pintype "passive"))
    )
    (net (code "188") (name "unconnected-(JP5-Pad5)") (class "Default")
      (node (ref "JP5") (pin "5") (pinfunction "5_5") (pintype "passive"))
    )
    (net (code "189") (name "unconnected-(JP5-Pad6)") (class "Default")
      (node (ref "JP5") (pin "6") (pinfunction "6_6") (pintype "passive"))
    )
    (net (code "190") (name "unconnected-(JP5-Pad7)") (class "Default")
      (node (ref "JP5") (pin "7") (pinfunction "7_7") (pintype "passive"))
    )
    (net (code "191") (name "unconnected-(JP5-Pad8)") (class "Default")
      (node (ref "JP5") (pin "8") (pinfunction "8_8") (pintype "passive"))
    )
    (net (code "192") (name "unconnected-(JP5-Pad9)") (class "Default")
      (node (ref "JP5") (pin "9") (pinfunction "9_9") (pintype "passive"))
    )
    (net (code "193") (name "unconnected-(JP5-Pad10)") (class "Default")
      (node (ref "JP5") (pin "10") (pinfunction "10_10") (pintype "passive"))
    )
    (net (code "194") (name "unconnected-(JP5-Pad11)") (class "Default")
      (node (ref "JP5") (pin "11") (pinfunction "11_11") (pintype "passive"))
    )
    (net (code "195") (name "unconnected-(JP5-Pad12)") (class "Default")
      (node (ref "JP5") (pin "12") (pinfunction "12_12") (pintype "passive"))
    )
    (net (code "196") (name "unconnected-(JP5-Pad13)") (class "Default")
      (node (ref "JP5") (pin "13") (pinfunction "13_13") (pintype "passive"))
    )
    (net (code "197") (name "unconnected-(JP5-Pad14)") (class "Default")
      (node (ref "JP5") (pin "14") (pinfunction "14_14") (pintype "passive"))
    )
    (net (code "198") (name "unconnected-(JP5-Pad15)") (class "Default")
      (node (ref "JP5") (pin "15") (pinfunction "15_15") (pintype "passive"))
    )
    (net (code "199") (name "unconnected-(JP5-Pad16)") (class "Default")
      (node (ref "JP5") (pin "16") (pinfunction "16_16") (pintype "passive"))
    )
    (net (code "200") (name "unconnected-(JP5-Pad17)") (class "Default")
      (node (ref "JP5") (pin "17") (pinfunction "17_17") (pintype "passive"))
    )
    (net (code "201") (name "unconnected-(JP5-Pad18)") (class "Default")
      (node (ref "JP5") (pin "18") (pinfunction "18_18") (pintype "passive"))
    )
    (net (code "202") (name "unconnected-(JP5-Pad19)") (class "Default")
      (node (ref "JP5") (pin "19") (pinfunction "19_19") (pintype "passive"))
    )
    (net (code "203") (name "unconnected-(JP5-Pad20)") (class "Default")
      (node (ref "JP5") (pin "20") (pinfunction "20_20") (pintype "passive"))
    )
    (net (code "204") (name "unconnected-(JP5-Pad21)") (class "Default")
      (node (ref "JP5") (pin "21") (pinfunction "21_21") (pintype "passive"))
    )
    (net (code "205") (name "unconnected-(JP5-Pad22)") (class "Default")
      (node (ref "JP5") (pin "22") (pinfunction "22_22") (pintype "passive"))
    )
    (net (code "206") (name "unconnected-(JP5-Pad23)") (class "Default")
      (node (ref "JP5") (pin "23") (pinfunction "23_23") (pintype "passive"))
    )
    (net (code "207") (name "unconnected-(JP5-Pad24)") (class "Default")
      (node (ref "JP5") (pin "24") (pinfunction "24_24") (pintype "passive"))
    )
    (net (code "208") (name "unconnected-(JP5-Pad25)") (class "Default")
      (node (ref "JP5") (pin "25") (pinfunction "25_25") (pintype "passive"))
    )
    (net (code "209") (name "unconnected-(JP5-Pad26)") (class "Default")
      (node (ref "JP5") (pin "26") (pinfunction "26_26") (pintype "passive"))
    )
    (net (code "210") (name "unconnected-(JP6-Pad1)") (class "Default")
      (node (ref "JP6") (pin "1") (pinfunction "1_1") (pintype "passive"))
    )
    (net (code "211") (name "unconnected-(JP6-Pad2)") (class "Default")
      (node (ref "JP6") (pin "2") (pinfunction "2_2") (pintype "passive"))
    )
    (net (code "212") (name "unconnected-(JP6-Pad3)") (class "Default")
      (node (ref "JP6") (pin "3") (pinfunction "3_3") (pintype "passive"))
    )
    (net (code "213") (name "unconnected-(JP6-Pad4)") (class "Default")
      (node (ref "JP6") (pin "4") (pinfunction "4_4") (pintype "passive"))
    )
    (net (code "214") (name "unconnected-(JP6-Pad5)") (class "Default")
      (node (ref "JP6") (pin "5") (pinfunction "5_5") (pintype "passive"))
    )
    (net (code "215") (name "unconnected-(JP6-Pad6)") (class "Default")
      (node (ref "JP6") (pin "6") (pinfunction "6_6") (pintype "passive"))
    )
    (net (code "216") (name "unconnected-(JP6-Pad7)") (class "Default")
      (node (ref "JP6") (pin "7") (pinfunction "7_7") (pintype "passive"))
    )
    (net (code "217") (name "unconnected-(JP6-Pad8)") (class "Default")
      (node (ref "JP6") (pin "8") (pinfunction "8_8") (pintype "passive"))
    )
    (net (code "218") (name "unconnected-(JP6-Pad9)") (class "Default")
      (node (ref "JP6") (pin "9") (pinfunction "9_9") (pintype "passive"))
    )
    (net (code "219") (name "unconnected-(JP6-Pad10)") (class "Default")
      (node (ref "JP6") (pin "10") (pinfunction "10_10") (pintype "passive"))
    )
    (net (code "220") (name "unconnected-(JP6-Pad11)") (class "Default")
      (node (ref "JP6") (pin "11") (pinfunction "11_11") (pintype "passive"))
    )
    (net (code "221") (name "unconnected-(JP6-Pad12)") (class "Default")
      (node (ref "JP6") (pin "12") (pinfunction "12_12") (pintype "passive"))
    )
    (net (code "222") (name "unconnected-(JP6-Pad13)") (class "Default")
      (node (ref "JP6") (pin "13") (pinfunction "13_13") (pintype "passive"))
    )
    (net (code "223") (name "unconnected-(JP6-Pad14)") (class "Default")
      (node (ref "JP6") (pin "14") (pinfunction "14_14") (pintype "passive"))
    )
    (net (code "224") (name "unconnected-(JP6-Pad15)") (class "Default")
      (node (ref "JP6") (pin "15") (pinfunction "15_15") (pintype "passive"))
    )
    (net (code "225") (name "unconnected-(JP6-Pad16)") (class "Default")
      (node (ref "JP6") (pin "16") (pinfunction "16_16") (pintype "passive"))
    )
    (net (code "226") (name "unconnected-(JP6-Pad17)") (class "Default")
      (node (ref "JP6") (pin "17") (pinfunction "17_17") (pintype "passive"))
    )
    (net (code "227") (name "unconnected-(JP6-Pad18)") (class "Default")
      (node (ref "JP6") (pin "18") (pinfunction "18_18") (pintype "passive"))
    )
    (net (code "228") (name "unconnected-(JP6-Pad19)") (class "Default")
      (node (ref "JP6") (pin "19") (pinfunction "19_19") (pintype "passive"))
    )
    (net (code "229") (name "unconnected-(JP6-Pad20)") (class "Default")
      (node (ref "JP6") (pin "20") (pinfunction "20_20") (pintype "passive"))
    )
    (net (code "230") (name "unconnected-(JP6-Pad21)") (class "Default")
      (node (ref "JP6") (pin "21") (pinfunction "21_21") (pintype "passive"))
    )
    (net (code "231") (name "unconnected-(JP6-Pad22)") (class "Default")
      (node (ref "JP6") (pin "22") (pinfunction "22_22") (pintype "passive"))
    )
    (net (code "232") (name "unconnected-(JP6-Pad23)") (class "Default")
      (node (ref "JP6") (pin "23") (pinfunction "23_23") (pintype "passive"))
    )
    (net (code "233") (name "unconnected-(JP6-Pad24)") (class "Default")
      (node (ref "JP6") (pin "24") (pinfunction "24_24") (pintype "passive"))
    )
    (net (code "234") (name "unconnected-(JP6-Pad25)") (class "Default")
      (node (ref "JP6") (pin "25") (pinfunction "25_25") (pintype "passive"))
    )
    (net (code "235") (name "unconnected-(JP6-Pad26)") (class "Default")
      (node (ref "JP6") (pin "26") (pinfunction "26_26") (pintype "passive"))
    )
    (net (code "236") (name "unconnected-(JP7-Pad1)") (class "Default")
      (node (ref "JP7") (pin "1") (pinfunction "1_1") (pintype "passive"))
    )
    (net (code "237") (name "unconnected-(JP7-Pad2)") (class "Default")
      (node (ref "JP7") (pin "2") (pinfunction "2_2") (pintype "passive"))
    )
    (net (code "238") (name "unconnected-(JP7-Pad3)") (class "Default")
      (node (ref "JP7") (pin "3") (pinfunction "3_3") (pintype "passive"))
    )
    (net (code "239") (name "unconnected-(JP7-Pad4)") (class "Default")
      (node (ref "JP7") (pin "4") (pinfunction "4_4") (pintype "passive"))
    )
    (net (code "240") (name "unconnected-(JP7-Pad5)") (class "Default")
      (node (ref "JP7") (pin "5") (pinfunction "5_5") (pintype "passive"))
    )
    (net (code "241") (name "unconnected-(JP7-Pad6)") (class "Default")
      (node (ref "JP7") (pin "6") (pinfunction "6_6") (pintype "passive"))
    )
    (net (code "242") (name "unconnected-(JP7-Pad7)") (class "Default")
      (node (ref "JP7") (pin "7") (pinfunction "7_7") (pintype "passive"))
    )
    (net (code "243") (name "unconnected-(JP7-Pad8)") (class "Default")
      (node (ref "JP7") (pin "8") (pinfunction "8_8") (pintype "passive"))
    )
    (net (code "244") (name "unconnected-(JP7-Pad9)") (class "Default")
      (node (ref "JP7") (pin "9") (pinfunction "9_9") (pintype "passive"))
    )
    (net (code "245") (name "unconnected-(JP7-Pad10)") (class "Default")
      (node (ref "JP7") (pin "10") (pinfunction "10_10") (pintype "passive"))
    )
    (net (code "246") (name "unconnected-(JP7-Pad11)") (class "Default")
      (node (ref "JP7") (pin "11") (pinfunction "11_11") (pintype "passive"))
    )
    (net (code "247") (name "unconnected-(JP7-Pad12)") (class "Default")
      (node (ref "JP7") (pin "12") (pinfunction "12_12") (pintype "passive"))
    )
    (net (code "248") (name "unconnected-(JP7-Pad13)") (class "Default")
      (node (ref "JP7") (pin "13") (pinfunction "13_13") (pintype "passive"))
    )
    (net (code "249") (name "unconnected-(JP7-Pad14)") (class "Default")
      (node (ref "JP7") (pin "14") (pinfunction "14_14") (pintype "passive"))
    )
    (net (code "250") (name "unconnected-(JP7-Pad15)") (class "Default")
      (node (ref "JP7") (pin "15") (pinfunction "15_15") (pintype "passive"))
    )
    (net (code "251") (name "unconnected-(JP7-Pad16)") (class "Default")
      (node (ref "JP7") (pin "16") (pinfunction "16_16") (pintype "passive"))
    )
    (net (code "252") (name "unconnected-(JP7-Pad17)") (class "Default")
      (node (ref "JP7") (pin "17") (pinfunction "17_17") (pintype "passive"))
    )
    (net (code "253") (name "unconnected-(JP7-Pad18)") (class "Default")
      (node (ref "JP7") (pin "18") (pinfunction "18_18") (pintype "passive"))
    )
    (net (code "254") (name "unconnected-(JP8-Pad1)") (class "Default")
      (node (ref "JP8") (pin "1") (pinfunction "1_1") (pintype "passive"))
    )
    (net (code "255") (name "unconnected-(JP8-Pad2)") (class "Default")
      (node (ref "JP8") (pin "2") (pinfunction "2_2") (pintype "passive"))
    )
    (net (code "256") (name "unconnected-(JP8-Pad3)") (class "Default")
      (node (ref "JP8") (pin "3") (pinfunction "3_3") (pintype "passive"))
    )
    (net (code "257") (name "unconnected-(JP8-Pad4)") (class "Default")
      (node (ref "JP8") (pin "4") (pinfunction "4_4") (pintype "passive"))
    )
    (net (code "258") (name "unconnected-(JP8-Pad5)") (class "Default")
      (node (ref "JP8") (pin "5") (pinfunction "5_5") (pintype "passive"))
    )
    (net (code "259") (name "unconnected-(JP8-Pad6)") (class "Default")
      (node (ref "JP8") (pin "6") (pinfunction "6_6") (pintype "passive"))
    )
    (net (code "260") (name "unconnected-(JP8-Pad7)") (class "Default")
      (node (ref "JP8") (pin "7") (pinfunction "7_7") (pintype "passive"))
    )
    (net (code "261") (name "unconnected-(JP8-Pad8)") (class "Default")
      (node (ref "JP8") (pin "8") (pinfunction "8_8") (pintype "passive"))
    )
    (net (code "262") (name "unconnected-(JP8-Pad9)") (class "Default")
      (node (ref "JP8") (pin "9") (pinfunction "9_9") (pintype "passive"))
    )
    (net (code "263") (name "unconnected-(JP8-Pad10)") (class "Default")
      (node (ref "JP8") (pin "10") (pinfunction "10_10") (pintype "passive"))
    )
    (net (code "264") (name "unconnected-(JP8-Pad11)") (class "Default")
      (node (ref "JP8") (pin "11") (pinfunction "11_11") (pintype "passive"))
    )
    (net (code "265") (name "unconnected-(JP8-Pad12)") (class "Default")
      (node (ref "JP8") (pin "12") (pinfunction "12_12") (pintype "passive"))
    )
    (net (code "266") (name "unconnected-(PWMH-Pad1)") (class "Default")
      (node (ref "PWMH") (pin "1") (pinfunction "1_1") (pintype "passive"))
    )
    (net (code "267") (name "unconnected-(PWMH-Pad2)") (class "Default")
      (node (ref "PWMH") (pin "2") (pinfunction "2_2") (pintype "passive"))
    )
    (net (code "268") (name "unconnected-(PWMH-Pad3)") (class "Default")
      (node (ref "PWMH") (pin "3") (pinfunction "3_3") (pintype "passive"))
    )
    (net (code "269") (name "unconnected-(PWMH-Pad4)") (class "Default")
      (node (ref "PWMH") (pin "4") (pinfunction "4_4") (pintype "passive"))
    )
    (net (code "270") (name "unconnected-(PWMH-Pad5)") (class "Default")
      (node (ref "PWMH") (pin "5") (pinfunction "5_5") (pintype "passive"))
    )
    (net (code "271") (name "unconnected-(PWMH-Pad6)") (class "Default")
      (node (ref "PWMH") (pin "6") (pinfunction "6_6") (pintype "passive"))
    )
    (net (code "272") (name "unconnected-(PWMH-Pad8)") (class "Default")
      (node (ref "PWMH") (pin "8") (pinfunction "8_8") (pintype "passive"))
    )
    (net (code "273") (name "unconnected-(SV1-Pad6)") (class "Default")
      (node (ref "SV1") (pin "6") (pinfunction "6_6") (pintype "passive"))
    )
    (net (code "274") (name "unconnected-(SV1-Pad23)") (class "Default")
      (node (ref "SV1") (pin "23") (pinfunction "23_23") (pintype "passive"))
    )
    (net (code "275") (name "unconnected-(SV1-Pad29)") (class "Default")
      (node (ref "SV1") (pin "29") (pinfunction "29_29") (pintype "passive"))
    )
    (net (code "276") (name "unconnected-(SV1-Pad31)") (class "Default")
      (node (ref "SV1") (pin "31") (pinfunction "31_31") (pintype "passive"))
    )
    (net (code "277") (name "unconnected-(SV1-Pad32)") (class "Default")
      (node (ref "SV1") (pin "32") (pinfunction "32_32") (pintype "passive"))
    )
    (net (code "278") (name "unconnected-(SV1-Pad33)") (class "Default")
      (node (ref "SV1") (pin "33") (pinfunction "33_33") (pintype "passive"))
    )
    (net (code "279") (name "unconnected-(SV1-Pad35)") (class "Default")
      (node (ref "SV1") (pin "35") (pinfunction "35_35") (pintype "passive"))
    )
    (net (code "280") (name "unconnected-(SV1-Pad36)") (class "Default")
      (node (ref "SV1") (pin "36") (pinfunction "36_36") (pintype "passive"))
    )
    (net (code "281") (name "unconnected-(SV1-Pad37)") (class "Default")
      (node (ref "SV1") (pin "37") (pinfunction "37_37") (pintype "passive"))
    )
    (net (code "282") (name "unconnected-(SV1-Pad39)") (class "Default")
      (node (ref "SV1") (pin "39") (pinfunction "39_39") (pintype "passive"))
    )
    (net (code "283") (name "unconnected-(SV1-Pad40)") (class "Default")
      (node (ref "SV1") (pin "40") (pinfunction "40_40") (pintype "passive"))
    )
    (net (code "284") (name "unconnected-(XIO-Pad1)") (class "Default")
      (node (ref "XIO") (pin "1") (pinfunction "1_1") (pintype "passive"))
    )
    (net (code "285") (name "unconnected-(XIO-Pad2)") (class "Default")
      (node (ref "XIO") (pin "2") (pinfunction "2_2") (pintype "passive"))
    )
    (net (code "286") (name "unconnected-(XIO-Pad23)") (class "Default")
      (node (ref "XIO") (pin "23") (pinfunction "23_23") (pintype "passive"))
    )
    (net (code "287") (name "unconnected-(XIO-Pad24)") (class "Default")
      (node (ref "XIO") (pin "24") (pinfunction "24_24") (pintype "passive"))
    )
    (net (code "288") (name "unconnected-(XIO-Pad25)") (class "Default")
      (node (ref "XIO") (pin "25") (pinfunction "25_25") (pintype "passive"))
    )
    (net (code "289") (name "unconnected-(XIO-Pad26)") (class "Default")
      (node (ref "XIO") (pin "26") (pinfunction "26_26") (pintype "passive"))
    )
    (net (code "290") (name "unconnected-(XIO-Pad27)") (class "Default")
      (node (ref "XIO") (pin "27") (pinfunction "27_27") (pintype "passive"))
    )
    (net (code "291") (name "unconnected-(XIO-Pad28)") (class "Default")
      (node (ref "XIO") (pin "28") (pinfunction "28_28") (pintype "passive"))
    )
    (net (code "292") (name "unconnected-(XIO-Pad29)") (class "Default")
      (node (ref "XIO") (pin "29") (pinfunction "29_29") (pintype "passive"))
    )
    (net (code "293") (name "unconnected-(XIO-Pad30)") (class "Default")
      (node (ref "XIO") (pin "30") (pinfunction "30_30") (pintype "passive"))
    )
    (net (code "294") (name "unconnected-(XIO-Pad31)") (class "Default")
      (node (ref "XIO") (pin "31") (pinfunction "31_31") (pintype "passive"))
    )
    (net (code "295") (name "unconnected-(XIO-Pad32)") (class "Default")
      (node (ref "XIO") (pin "32") (pinfunction "32_32") (pintype "passive"))
    )
    (net (code "296") (name "unconnected-(XIO-Pad33)") (class "Default")
      (node (ref "XIO") (pin "33") (pinfunction "33_33") (pintype "passive"))
    )
    (net (code "297") (name "unconnected-(XIO-Pad34)") (class "Default")
      (node (ref "XIO") (pin "34") (pinfunction "34_34") (pintype "passive"))
    )
    (net (code "298") (name "unconnected-(XIO-Pad35)") (class "Default")
      (node (ref "XIO") (pin "35") (pinfunction "35_35") (pintype "passive"))
    )
    (net (code "299") (name "unconnected-(XIO-Pad36)") (class "Default")
      (node (ref "XIO") (pin "36") (pinfunction "36_36") (pintype "passive"))
    )
  )
)
